# pmod-dual-bar-graph.net
KiCad netlist of a schematic drawn in EAGLE
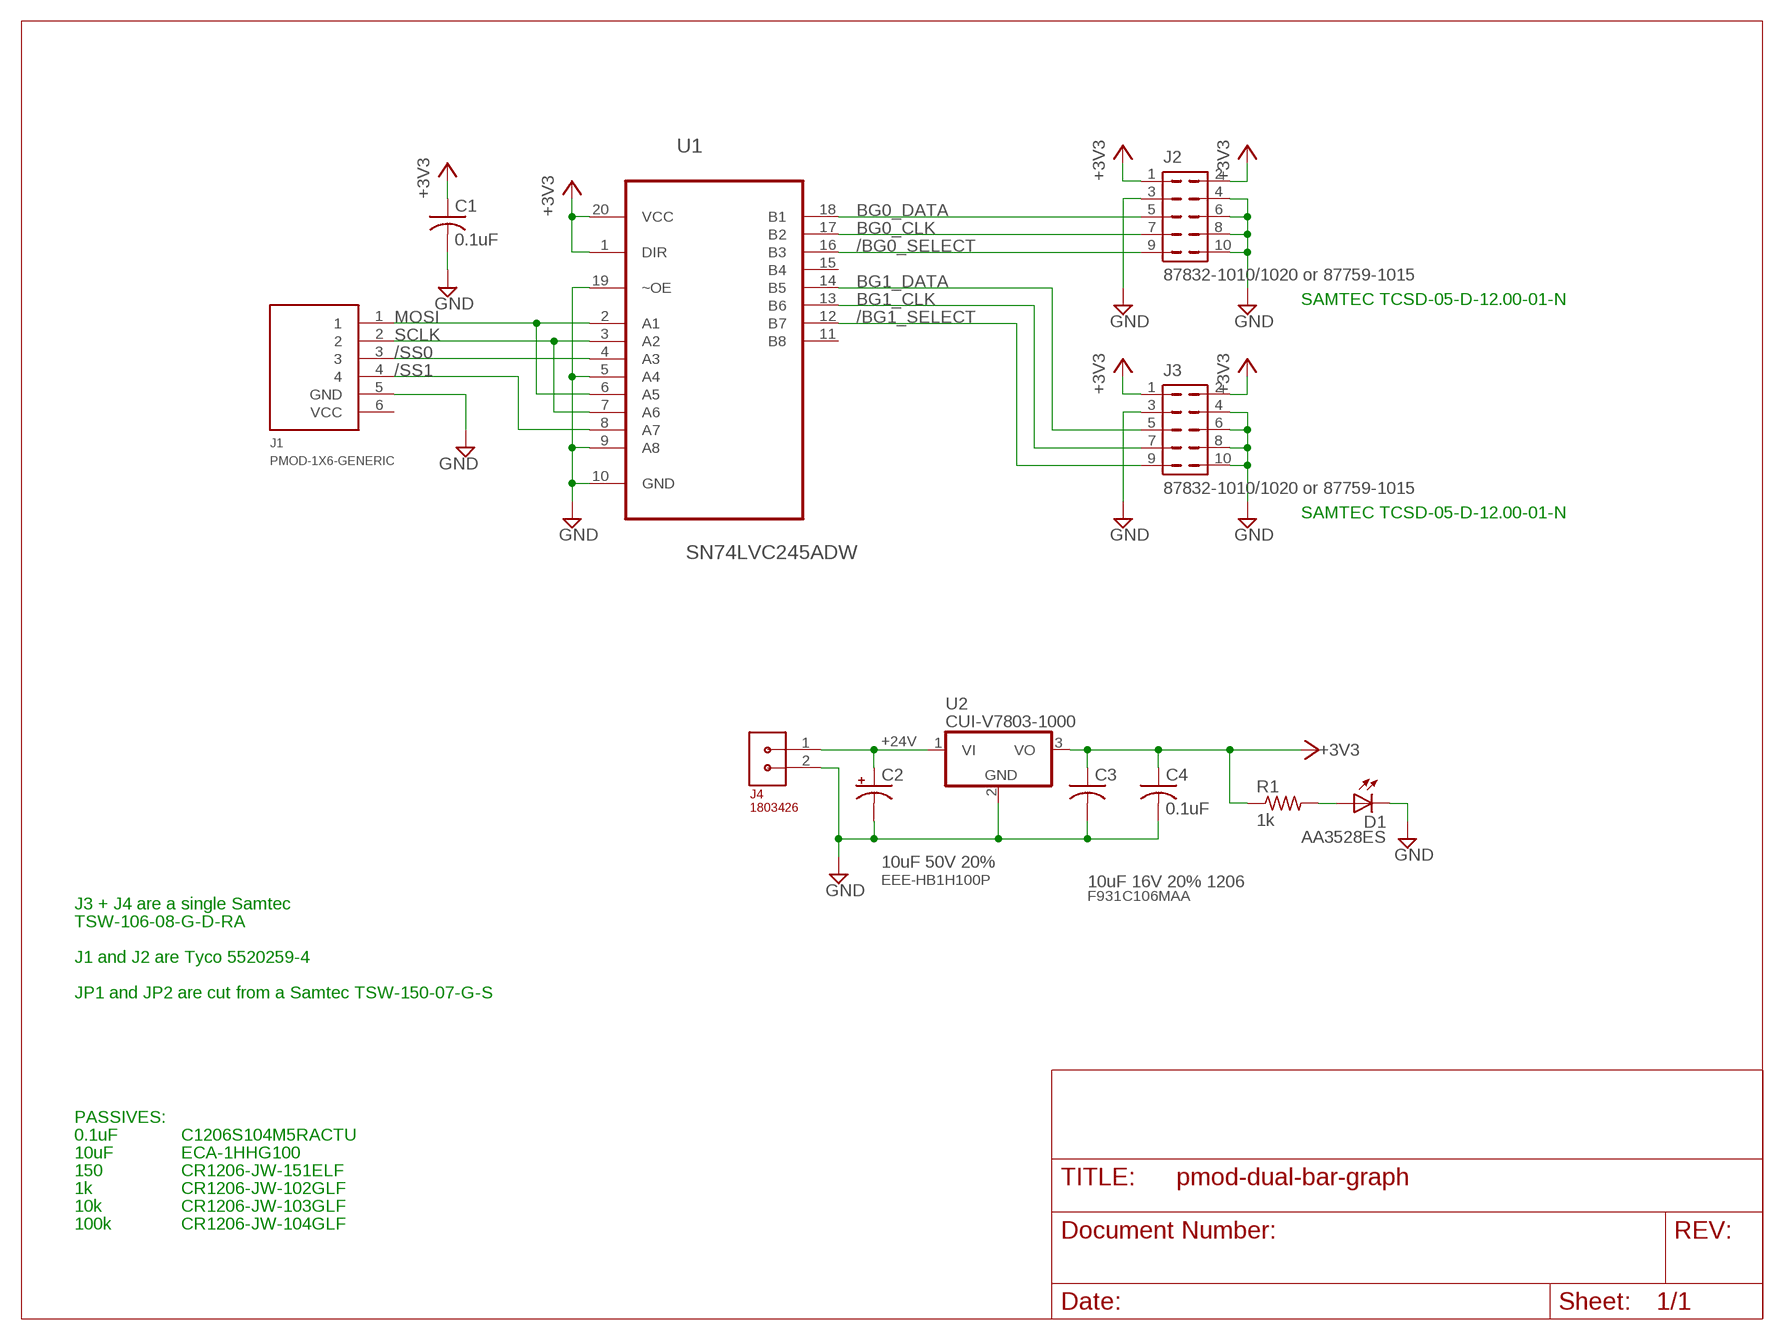
[diagram p0: schematic, sheet 1]

(export (version "E")
  (design (tool "Eeschema 10.0.6"))
  (components
    (comp (ref "C1")
      (value "0.1uF")
      (footprint "eagle-import:C1206")
      (libsource (lib "eagle-import") (part "C-USC1206"))
    )
    (comp (ref "C2")
      (value "10uF 50V 20%")
      (footprint "eagle-import:PANASONIC_D")
      (libsource (lib "eagle-import") (part "CPOL-USD"))
    )
    (comp (ref "C3")
      (value "10uF 16V 20% 1206")
      (footprint "eagle-import:C1206")
      (libsource (lib "eagle-import") (part "C-USC1206"))
    )
    (comp (ref "C4")
      (value "0.1uF")
      (footprint "eagle-import:C1206")
      (libsource (lib "eagle-import") (part "C-USC1206"))
    )
    (comp (ref "D1")
      (value "AA3528ES")
      (footprint "eagle-import:KA-3528ASYC")
      (libsource (lib "eagle-import") (part "LEDKA-3528ASYC"))
    )
    (comp (ref "J1")
      (value "PMOD-1X6-GENERIC")
      (footprint "eagle-import:CON-PMOD-1X6")
      (libsource (lib "eagle-import") (part "PMOD-1X6-GENERIC"))
    )
    (comp (ref "J2")
      (value "87832-1010/1020 or 87759-1015")
      (footprint "eagle-import:87832-10")
      (libsource (lib "eagle-import") (part "87832-10"))
    )
    (comp (ref "J3")
      (value "87832-1010/1020 or 87759-1015")
      (footprint "eagle-import:87832-10")
      (libsource (lib "eagle-import") (part "87832-10"))
    )
    (comp (ref "J4")
      (value "1803426")
      (footprint "eagle-import:CON-PHOENIX-1803426-3.81-1X2")
      (libsource (lib "eagle-import") (part "CON-3.81MM-1X2-PHOENIX-1803426"))
    )
    (comp (ref "R1")
      (value "1k")
      (footprint "eagle-import:R1206")
      (libsource (lib "eagle-import") (part "R-US_R1206"))
    )
    (comp (ref "U1")
      (value "SN74LVC245ADW")
      (footprint "eagle-import:SOIC127P1030X265-20N")
      (libsource (lib "eagle-import") (part "SN74LVC245ADW"))
    )
    (comp (ref "U2")
      (value "CUI-V7803-1000")
      (footprint "eagle-import:CUI-78XX-1000")
      (libsource (lib "eagle-import") (part "CUI-V7803-1000"))
    )
  )
  (nets
    (net (code "1") (name "+3V3") (class "Default")
      (node (ref "C1") (pin "1") (pinfunction "1_1") (pintype "passive"))
      (node (ref "C3") (pin "1") (pinfunction "1_1") (pintype "passive"))
      (node (ref "C4") (pin "1") (pinfunction "1_1") (pintype "passive"))
      (node (ref "J2") (pin "1") (pinfunction "1_1") (pintype "passive"))
      (node (ref "J2") (pin "2") (pinfunction "2_2") (pintype "passive"))
      (node (ref "J3") (pin "1") (pinfunction "1_1") (pintype "passive"))
      (node (ref "J3") (pin "2") (pinfunction "2_2") (pintype "passive"))
      (node (ref "R1") (pin "1") (pinfunction "1_1") (pintype "passive"))
      (node (ref "U1") (pin "1") (pinfunction "DIR_1") (pintype "input"))
      (node (ref "U1") (pin "20") (pinfunction "VCC_20") (pintype "power_in"))
      (node (ref "U2") (pin "3") (pinfunction "VO_3") (pintype "passive"))
    )
    (net (code "2") (name "/+24V") (class "Default")
      (node (ref "C2") (pin "+") (pinfunction "+_+") (pintype "passive"))
      (node (ref "J4") (pin "1") (pinfunction "1_1") (pintype "bidirectional"))
      (node (ref "U2") (pin "1") (pinfunction "VI_1") (pintype "input"))
    )
    (net (code "3") (name "/BG0_CLK") (class "Default")
      (node (ref "J2") (pin "7") (pinfunction "7_7") (pintype "passive"))
      (node (ref "U1") (pin "17") (pinfunction "B2_17") (pintype "bidirectional"))
    )
    (net (code "4") (name "/BG0_DATA") (class "Default")
      (node (ref "J2") (pin "5") (pinfunction "5_5") (pintype "passive"))
      (node (ref "U1") (pin "18") (pinfunction "B1_18") (pintype "bidirectional"))
    )
    (net (code "5") (name "/BG1_CLK") (class "Default")
      (node (ref "J3") (pin "7") (pinfunction "7_7") (pintype "passive"))
      (node (ref "U1") (pin "13") (pinfunction "B6_13") (pintype "bidirectional"))
    )
    (net (code "6") (name "/BG1_DATA") (class "Default")
      (node (ref "J3") (pin "5") (pinfunction "5_5") (pintype "passive"))
      (node (ref "U1") (pin "14") (pinfunction "B5_14") (pintype "bidirectional"))
    )
    (net (code "7") (name "/MOSI") (class "Default")
      (node (ref "J1") (pin "1") (pinfunction "1_1") (pintype "bidirectional"))
      (node (ref "U1") (pin "2") (pinfunction "A1_2") (pintype "bidirectional"))
      (node (ref "U1") (pin "6") (pinfunction "A5_6") (pintype "bidirectional"))
    )
    (net (code "8") (name "/SCLK") (class "Default")
      (node (ref "J1") (pin "2") (pinfunction "2_2") (pintype "bidirectional"))
      (node (ref "U1") (pin "3") (pinfunction "A2_3") (pintype "bidirectional"))
      (node (ref "U1") (pin "7") (pinfunction "A6_7") (pintype "bidirectional"))
    )
    (net (code "9") (name "/{slash}BG0_SELECT") (class "Default")
      (node (ref "J2") (pin "9") (pinfunction "9_9") (pintype "passive"))
      (node (ref "U1") (pin "16") (pinfunction "B3_16") (pintype "bidirectional"))
    )
    (net (code "10") (name "/{slash}BG1_SELECT") (class "Default")
      (node (ref "J3") (pin "9") (pinfunction "9_9") (pintype "passive"))
      (node (ref "U1") (pin "12") (pinfunction "B7_12") (pintype "bidirectional"))
    )
    (net (code "11") (name "/{slash}SS0") (class "Default")
      (node (ref "J1") (pin "3") (pinfunction "3_3") (pintype "bidirectional"))
      (node (ref "U1") (pin "4") (pinfunction "A3_4") (pintype "bidirectional"))
    )
    (net (code "12") (name "/{slash}SS1") (class "Default")
      (node (ref "J1") (pin "4") (pinfunction "4_4") (pintype "bidirectional"))
      (node (ref "U1") (pin "8") (pinfunction "A7_8") (pintype "bidirectional"))
    )
    (net (code "13") (name "GND") (class "Default")
      (node (ref "C1") (pin "2") (pinfunction "2_2") (pintype "passive"))
      (node (ref "C2") (pin "-") (pinfunction "-_-") (pintype "passive"))
      (node (ref "C3") (pin "2") (pinfunction "2_2") (pintype "passive"))
      (node (ref "C4") (pin "2") (pinfunction "2_2") (pintype "passive"))
      (node (ref "D1") (pin "C") (pinfunction "C_C") (pintype "passive"))
      (node (ref "J1") (pin "5") (pinfunction "GND_5") (pintype "power_in"))
      (node (ref "J2") (pin "10") (pinfunction "10_10") (pintype "passive"))
      (node (ref "J2") (pin "3") (pinfunction "3_3") (pintype "passive"))
      (node (ref "J2") (pin "4") (pinfunction "4_4") (pintype "passive"))
      (node (ref "J2") (pin "6") (pinfunction "6_6") (pintype "passive"))
      (node (ref "J2") (pin "8") (pinfunction "8_8") (pintype "passive"))
      (node (ref "J3") (pin "10") (pinfunction "10_10") (pintype "passive"))
      (node (ref "J3") (pin "3") (pinfunction "3_3") (pintype "passive"))
      (node (ref "J3") (pin "4") (pinfunction "4_4") (pintype "passive"))
      (node (ref "J3") (pin "6") (pinfunction "6_6") (pintype "passive"))
      (node (ref "J3") (pin "8") (pinfunction "8_8") (pintype "passive"))
      (node (ref "J4") (pin "2") (pinfunction "2_2") (pintype "bidirectional"))
      (node (ref "U1") (pin "10") (pinfunction "GND_10") (pintype "passive"))
      (node (ref "U1") (pin "19") (pinfunction "~{OE}_19") (pintype "input"))
      (node (ref "U1") (pin "5") (pinfunction "A4_5") (pintype "bidirectional"))
      (node (ref "U1") (pin "9") (pinfunction "A8_9") (pintype "bidirectional"))
      (node (ref "U2") (pin "2") (pinfunction "GND_2") (pintype "passive"))
    )
    (net (code "14") (name "Net-(D1-PadA)") (class "Default")
      (node (ref "D1") (pin "A") (pinfunction "A_A") (pintype "passive"))
      (node (ref "R1") (pin "2") (pinfunction "2_2") (pintype "passive"))
    )
    (net (code "15") (name "unconnected-(J1-VCC-Pad6)") (class "Default")
      (node (ref "J1") (pin "6") (pinfunction "VCC_6") (pintype "bidirectional"))
    )
    (net (code "16") (name "unconnected-(U1-B4-Pad15)") (class "Default")
      (node (ref "U1") (pin "15") (pinfunction "B4_15") (pintype "bidirectional"))
    )
    (net (code "17") (name "unconnected-(U1-B8-Pad11)") (class "Default")
      (node (ref "U1") (pin "11") (pinfunction "B8_11") (pintype "bidirectional"))
    )
  )
)
